# Sheet2.net
KiCad netlist of a schematic drawn in Altium Designer
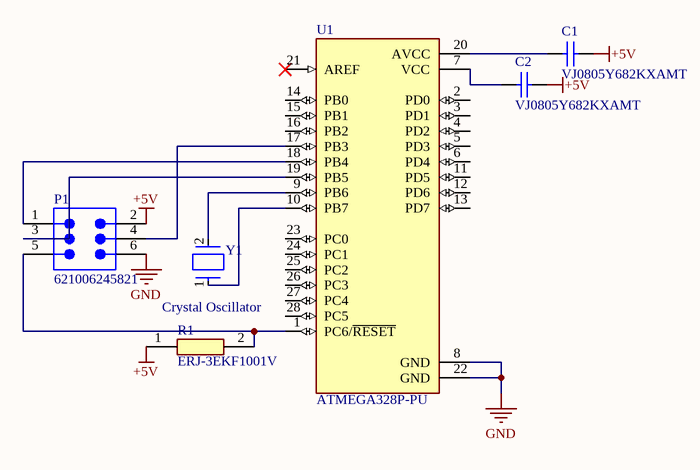
[diagram p0: Sheet2.SchDoc]

(export (version "E")
  (design (tool "Eeschema 10.0.6"))
  (components
    (comp (ref "C1")
      (value "VJ0805Y682KXAMT")
      (footprint "CAPC2013X145X48ML20T23")
      (fields (field (name "MANUFACTURER") "Vitramon"))
      (libsource (lib "Altium Content Vault") (part "CAP"))
    )
    (comp (ref "C2")
      (value "VJ0805Y682KXAMT")
      (footprint "CAPC2013X145X48ML20T23")
      (fields (field (name "MANUFACTURER") "Vitramon"))
      (libsource (lib "Altium Content Vault") (part "CAP"))
    )
    (comp (ref "P1")
      (value "621006245821")
      (footprint "621006245821")
      (description "SMT Vertical Pin Header WR-PHD, Pitch 2.00 mm, Dual Row, 6 pins")
      (libsource (lib "Altium Content Vault") (part "Header_Male_2R_06P"))
    )
    (comp (ref "R1")
      (value "ERJ-3EKF1001V")
      (footprint "SamacSys:RESC1608X55N")
      (description "Resistor")
      (fields (field (name "MOUSER PART NUMBER") "667-ERJ-3EKF1001V"))
      (libsource (lib "*") (part "ERJ-3EKF1001V"))
    )
    (comp (ref "U1")
      (value "ATMEGA328P-PU")
      (footprint "DIP794W46P254L2967H457Q28B")
      (description "ATmega Series 20 MHz 32 KB Flash 2 KB SRAM 8-Bit Microcontroller - DIP-28")
      (libsource (lib "ATMEGA328P-PU") (part "ATMEGA328P-PU"))
    )
    (comp (ref "Y1")
      (value "Crystal Oscillator")
      (footprint "FP-AB26TRB-MFG")
      (description "CRYSTAL 32.7680KHZ 12.5PF TH")
      (fields (field (name "TOLERANCE") "20ppm"))
      (libsource (lib "Altium Content Vault") (part "c23a69dc6c9e2f18f2079038eb95dd1"))
    )
  )
  (nets
    (net (code "1") (name "+5V") (class "Default")
      (node (ref "C1") (pin "2") (pinfunction "2_2") (pintype "passive"))
      (node (ref "C2") (pin "2") (pinfunction "2_2") (pintype "passive"))
      (node (ref "P1") (pin "2") (pinfunction "2_2") (pintype "passive"))
      (node (ref "R1") (pin "1") (pinfunction "1_1") (pintype "passive"))
    )
    (net (code "2") (name "GND") (class "Default")
      (node (ref "P1") (pin "6") (pinfunction "6_6") (pintype "passive"))
      (node (ref "U1") (pin "22") (pinfunction "GND_22") (pintype "power_in"))
      (node (ref "U1") (pin "8") (pinfunction "GND_8") (pintype "power_in"))
    )
    (net (code "3") (name "Net-(U1-AVCC)") (class "Default")
      (node (ref "C1") (pin "1") (pinfunction "1_1") (pintype "passive"))
      (node (ref "U1") (pin "20") (pinfunction "AVCC_20") (pintype "power_in"))
    )
    (net (code "4") (name "Net-(U1-PB3)") (class "Default")
      (node (ref "P1") (pin "4") (pinfunction "4_4") (pintype "passive"))
      (node (ref "U1") (pin "17") (pinfunction "PB3_17") (pintype "bidirectional"))
    )
    (net (code "5") (name "Net-(U1-PB4)") (class "Default")
      (node (ref "P1") (pin "1") (pinfunction "1_1") (pintype "passive"))
      (node (ref "U1") (pin "18") (pinfunction "PB4_18") (pintype "bidirectional"))
    )
    (net (code "6") (name "Net-(U1-PB5)") (class "Default")
      (node (ref "P1") (pin "3") (pinfunction "3_3") (pintype "passive"))
      (node (ref "U1") (pin "19") (pinfunction "PB5_19") (pintype "bidirectional"))
    )
    (net (code "7") (name "Net-(U1-PB6)") (class "Default")
      (node (ref "U1") (pin "9") (pinfunction "PB6_9") (pintype "bidirectional"))
      (node (ref "Y1") (pin "2") (pinfunction "2_2") (pintype "passive"))
    )
    (net (code "8") (name "Net-(U1-PB7)") (class "Default")
      (node (ref "U1") (pin "10") (pinfunction "PB7_10") (pintype "bidirectional"))
      (node (ref "Y1") (pin "1") (pinfunction "1_1") (pintype "passive"))
    )
    (net (code "9") (name "Net-(U1-PC6{slash}~{RESET})") (class "Default")
      (node (ref "P1") (pin "5") (pinfunction "5_5") (pintype "passive"))
      (node (ref "R1") (pin "2") (pinfunction "2_2") (pintype "passive"))
      (node (ref "U1") (pin "1") (pinfunction "PC6/~{RESET}_1") (pintype "bidirectional"))
    )
    (net (code "10") (name "Net-(U1-VCC)") (class "Default")
      (node (ref "C2") (pin "1") (pinfunction "1_1") (pintype "passive"))
      (node (ref "U1") (pin "7") (pinfunction "VCC_7") (pintype "power_in"))
    )
    (net (code "11") (name "unconnected-(U1-AREF-Pad21)") (class "Default")
      (node (ref "U1") (pin "21") (pinfunction "AREF_21") (pintype "input+no_connect"))
    )
    (net (code "12") (name "unconnected-(U1-PB0-Pad14)") (class "Default")
      (node (ref "U1") (pin "14") (pinfunction "PB0_14") (pintype "bidirectional"))
    )
    (net (code "13") (name "unconnected-(U1-PB1-Pad15)") (class "Default")
      (node (ref "U1") (pin "15") (pinfunction "PB1_15") (pintype "bidirectional"))
    )
    (net (code "14") (name "unconnected-(U1-PB2-Pad16)") (class "Default")
      (node (ref "U1") (pin "16") (pinfunction "PB2_16") (pintype "bidirectional"))
    )
    (net (code "15") (name "unconnected-(U1-PC0-Pad23)") (class "Default")
      (node (ref "U1") (pin "23") (pinfunction "PC0_23") (pintype "bidirectional"))
    )
    (net (code "16") (name "unconnected-(U1-PC1-Pad24)") (class "Default")
      (node (ref "U1") (pin "24") (pinfunction "PC1_24") (pintype "bidirectional"))
    )
    (net (code "17") (name "unconnected-(U1-PC2-Pad25)") (class "Default")
      (node (ref "U1") (pin "25") (pinfunction "PC2_25") (pintype "bidirectional"))
    )
    (net (code "18") (name "unconnected-(U1-PC3-Pad26)") (class "Default")
      (node (ref "U1") (pin "26") (pinfunction "PC3_26") (pintype "bidirectional"))
    )
    (net (code "19") (name "unconnected-(U1-PC4-Pad27)") (class "Default")
      (node (ref "U1") (pin "27") (pinfunction "PC4_27") (pintype "bidirectional"))
    )
    (net (code "20") (name "unconnected-(U1-PC5-Pad28)") (class "Default")
      (node (ref "U1") (pin "28") (pinfunction "PC5_28") (pintype "bidirectional"))
    )
    (net (code "21") (name "unconnected-(U1-PD0-Pad2)") (class "Default")
      (node (ref "U1") (pin "2") (pinfunction "PD0_2") (pintype "bidirectional"))
    )
    (net (code "22") (name "unconnected-(U1-PD1-Pad3)") (class "Default")
      (node (ref "U1") (pin "3") (pinfunction "PD1_3") (pintype "bidirectional"))
    )
    (net (code "23") (name "unconnected-(U1-PD2-Pad4)") (class "Default")
      (node (ref "U1") (pin "4") (pinfunction "PD2_4") (pintype "bidirectional"))
    )
    (net (code "24") (name "unconnected-(U1-PD3-Pad5)") (class "Default")
      (node (ref "U1") (pin "5") (pinfunction "PD3_5") (pintype "bidirectional"))
    )
    (net (code "25") (name "unconnected-(U1-PD4-Pad6)") (class "Default")
      (node (ref "U1") (pin "6") (pinfunction "PD4_6") (pintype "bidirectional"))
    )
    (net (code "26") (name "unconnected-(U1-PD5-Pad11)") (class "Default")
      (node (ref "U1") (pin "11") (pinfunction "PD5_11") (pintype "bidirectional"))
    )
    (net (code "27") (name "unconnected-(U1-PD6-Pad12)") (class "Default")
      (node (ref "U1") (pin "12") (pinfunction "PD6_12") (pintype "bidirectional"))
    )
    (net (code "28") (name "unconnected-(U1-PD7-Pad13)") (class "Default")
      (node (ref "U1") (pin "13") (pinfunction "PD7_13") (pintype "bidirectional"))
    )
  )
)
